# USB.net
KiCad netlist of a schematic drawn in Altium Designer
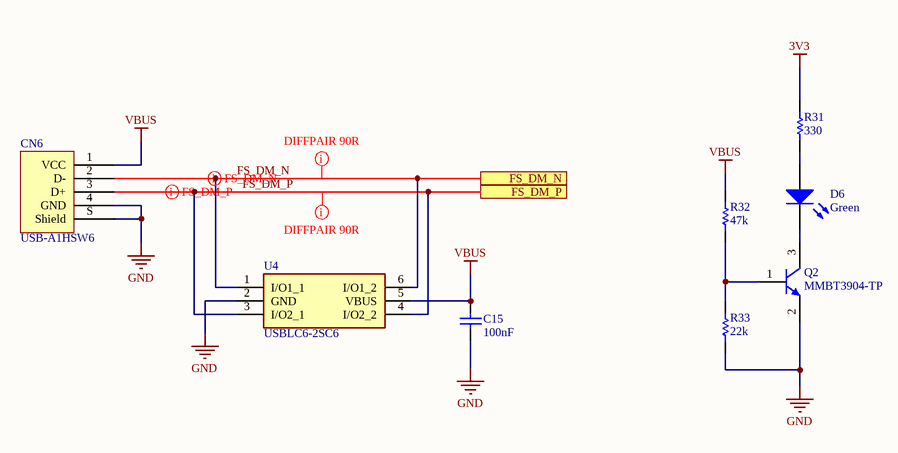
[diagram p0: USB.SchDoc]

(export (version "E")
  (design (tool "Eeschema 10.0.6"))
  (components
    (comp (ref "C15")
      (value "100nF")
      (footprint "1608[0603]")
      (description "Capacitor")
      (fields (field (name "Comment") "Cap") (field (name "PUBLISHER") "Altium Limited"))
      (libsource (lib "Miscellaneous Devices") (part "Cap"))
    )
    (comp (ref "CN6")
      (value "USB-A1HSW6")
      (footprint "ON SHORE TECHNOLOGY USB-A1HSW6")
      (description "CONN RCPT TYPEA 4POS R/A")
      (fields (field (name "MANUFACTURER") "On Shore Technology Inc."))
      (libsource (lib "Celestial Altium Library - altium_library") (part "USB 2.0 TYPE A"))
    )
    (comp (ref "D6")
      (value "Green")
      (footprint "1608[0603]")
      (description "Typical BLUE SiC LED")
      (fields (field (name "PUBLISHER") "Altium Limited"))
      (libsource (lib "Miscellaneous Devices") (part "LED3"))
    )
    (comp (ref "Q2")
      (value "MMBT3904-TP")
      (footprint "MCCSEMI SOT-23-3")
      (description "TRANS NPN 40V 0.2A SOT23")
      (fields (field (name "MANUFACTURER") "Micro Commercial Co"))
      (libsource (lib "Celestial Altium Library - altium_library") (part "MCCSEMI NPN SOT-23-3"))
    )
    (comp (ref "R31")
      (value "330")
      (footprint "1608[0603]")
      (description "Resistor")
      (fields (field (name "Comment") "Res1") (field (name "PUBLISHER") "Altium Limited"))
      (libsource (lib "Miscellaneous Devices") (part "Res1"))
    )
    (comp (ref "R32")
      (value "47k")
      (footprint "1608[0603]")
      (description "Resistor")
      (fields (field (name "Comment") "Res1") (field (name "PUBLISHER") "Altium Limited"))
      (libsource (lib "Miscellaneous Devices") (part "Res1"))
    )
    (comp (ref "R33")
      (value "22k")
      (footprint "1608[0603]")
      (description "Resistor")
      (fields (field (name "Comment") "Res1") (field (name "PUBLISHER") "Altium Limited"))
      (libsource (lib "Miscellaneous Devices") (part "Res1"))
    )
    (comp (ref "U4")
      (value "USBLC6-2SC6")
      (footprint "SamacSys:SOT95P280X145-6N")
      (description "Integrated Circuit")
      (fields (field (name "MOUSER PART NUMBER") "511-USBLC6-2SC6"))
      (libsource (lib "*") (part "USBLC6-2SC6"))
    )
  )
  (nets
    (net (code "1") (name "/FS_DM_N") (class "Default")
      (node (ref "CN6") (pin "2") (pinfunction "D-_2") (pintype "passive"))
      (node (ref "U4") (pin "1") (pinfunction "I/O1_1_1") (pintype "passive"))
      (node (ref "U4") (pin "6") (pinfunction "I/O1_2_6") (pintype "passive"))
    )
    (net (code "2") (name "/FS_DM_P") (class "Default")
      (node (ref "CN6") (pin "3") (pinfunction "D+_3") (pintype "passive"))
      (node (ref "U4") (pin "3") (pinfunction "I/O2_1_3") (pintype "passive"))
      (node (ref "U4") (pin "4") (pinfunction "I/O2_2_4") (pintype "passive"))
    )
    (net (code "3") (name "3V3") (class "Default")
      (node (ref "R31") (pin "2") (pinfunction "2_2") (pintype "passive"))
    )
    (net (code "4") (name "GND") (class "Default")
      (node (ref "C15") (pin "1") (pinfunction "1_1") (pintype "passive"))
      (node (ref "CN6") (pin "4") (pinfunction "GND_4") (pintype "passive"))
      (node (ref "CN6") (pin "S") (pinfunction "Shield_S") (pintype "passive"))
      (node (ref "Q2") (pin "2") (pinfunction "E_2") (pintype "passive"))
      (node (ref "R33") (pin "1") (pinfunction "1_1") (pintype "passive"))
      (node (ref "U4") (pin "2") (pinfunction "GND_2") (pintype "passive"))
    )
    (net (code "5") (name "Net-(D6-A)") (class "Default")
      (node (ref "D6") (pin "1") (pinfunction "A_1") (pintype "passive"))
      (node (ref "R31") (pin "1") (pinfunction "1_1") (pintype "passive"))
    )
    (net (code "6") (name "Net-(D6-K)") (class "Default")
      (node (ref "D6") (pin "2") (pinfunction "K_2") (pintype "passive"))
      (node (ref "Q2") (pin "3") (pinfunction "C_3") (pintype "passive"))
    )
    (net (code "7") (name "Net-(Q2-B)") (class "Default")
      (node (ref "Q2") (pin "1") (pinfunction "B_1") (pintype "passive"))
      (node (ref "R32") (pin "1") (pinfunction "1_1") (pintype "passive"))
      (node (ref "R33") (pin "2") (pinfunction "2_2") (pintype "passive"))
    )
    (net (code "8") (name "VBUS") (class "Default")
      (node (ref "C15") (pin "2") (pinfunction "2_2") (pintype "passive"))
      (node (ref "CN6") (pin "1") (pinfunction "VCC_1") (pintype "passive"))
      (node (ref "R32") (pin "2") (pinfunction "2_2") (pintype "passive"))
      (node (ref "U4") (pin "5") (pinfunction "VBUS_5") (pintype "passive"))
    )
  )
)
